# usb_and_power.net
KiCad netlist of a schematic drawn in Altium Designer
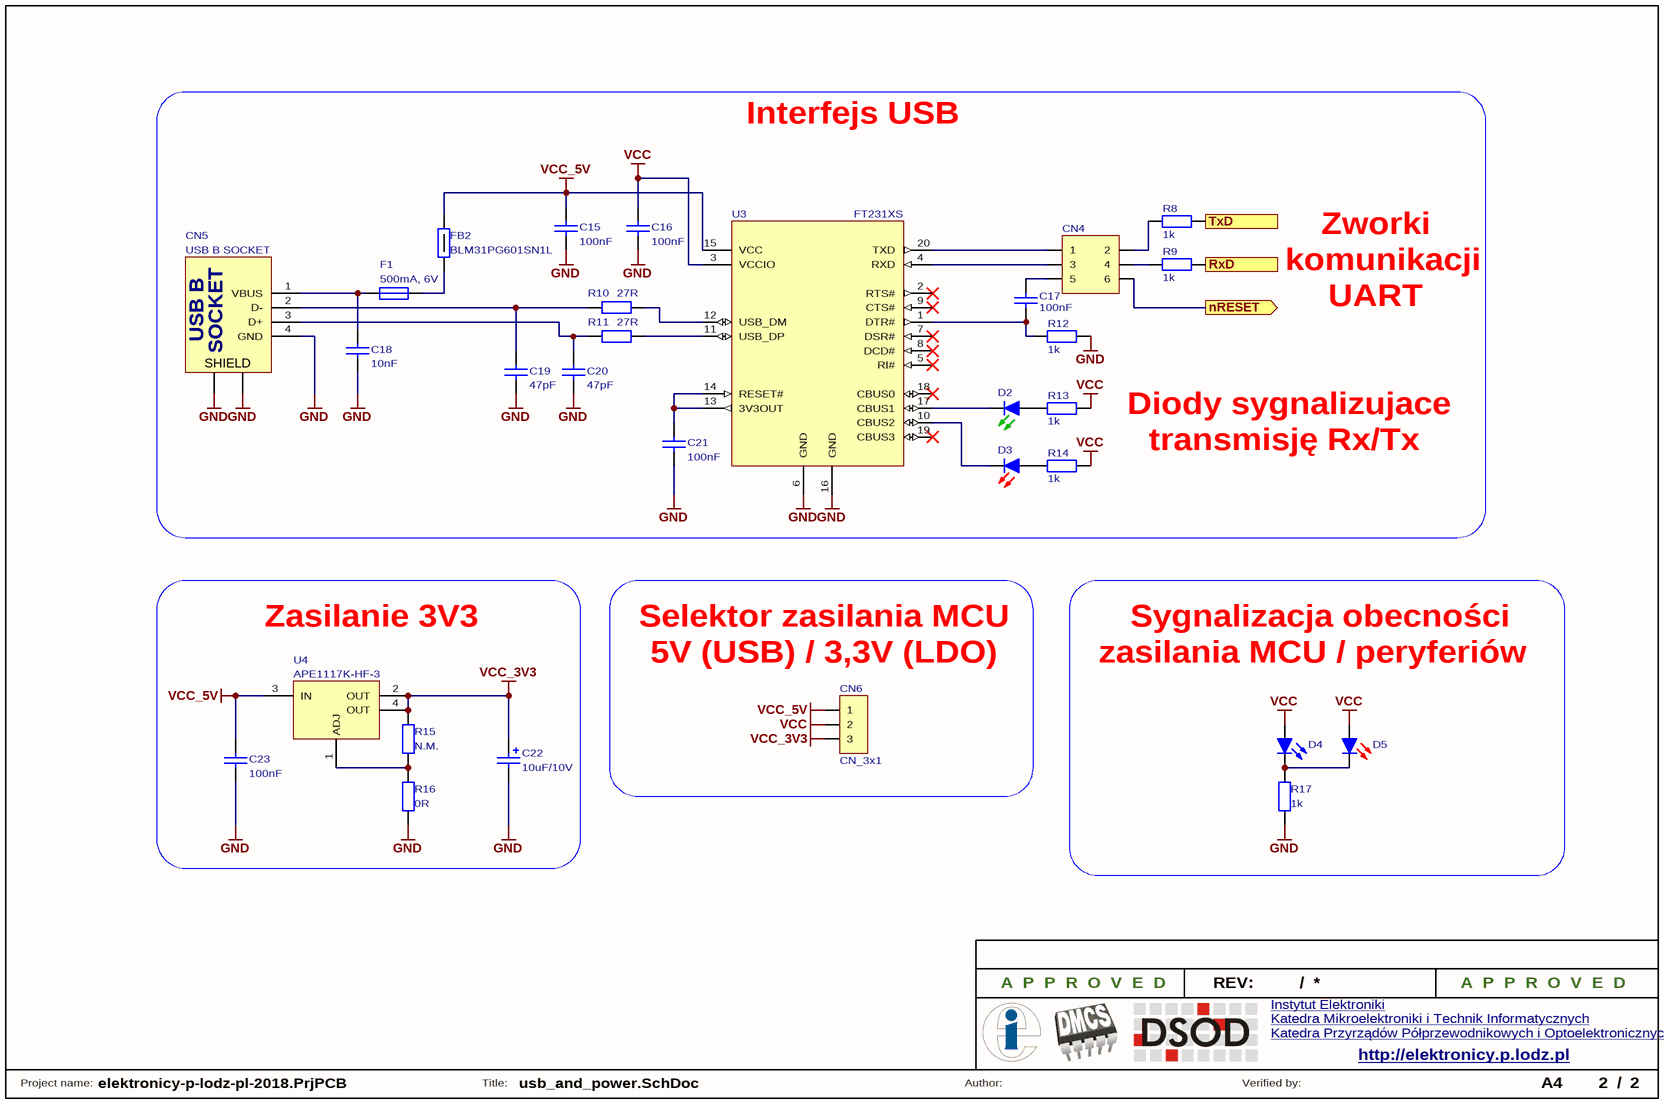
[diagram p0: usb_and_power.SchDoc]

(export (version "E")
  (design (tool "Eeschema 10.0.6"))
  (components
    (comp (ref "C15")
      (value "100nF")
      (footprint "C1206")
      (description "Capacitor")
      (libsource (lib "") (part "Cap_1"))
    )
    (comp (ref "C16")
      (value "100nF")
      (footprint "C1206")
      (description "Capacitor")
      (libsource (lib "") (part "Cap_1"))
    )
    (comp (ref "C17")
      (value "100nF")
      (footprint "C1206")
      (description "Capacitor")
      (libsource (lib "capacitors") (part "Cap"))
    )
    (comp (ref "C18")
      (value "10nF")
      (footprint "C1206")
      (description "Capacitor")
      (libsource (lib "") (part "Cap_1"))
    )
    (comp (ref "C19")
      (value "47pF")
      (footprint "C1206")
      (description "Capacitor")
      (libsource (lib "") (part "Cap_1"))
    )
    (comp (ref "C20")
      (value "47pF")
      (footprint "C1206")
      (description "Capacitor")
      (libsource (lib "") (part "Cap_1"))
    )
    (comp (ref "C21")
      (value "100nF")
      (footprint "C1206")
      (description "Capacitor")
      (libsource (lib "") (part "Cap_1"))
    )
    (comp (ref "C22")
      (value "10uF/10V")
      (footprint "SMDB")
      (description "Polarized Tantalum Capacitor")
      (libsource (lib "capacitors") (part "Cap Pol Tant"))
    )
    (comp (ref "C23")
      (value "100nF")
      (footprint "C1206")
      (description "Capacitor")
      (libsource (lib "capacitors") (part "Cap"))
    )
    (comp (ref "CN4") (value "*") (footprint "GP_3x2") (libsource (lib "goldpin_male") (part "CN_3x2")))
    (comp (ref "CN5")
      (value "USB B SOCKET")
      (footprint "USBB-G")
      (description "USB connector")
      (libsource (lib "usb") (part "USB B SOCKET"))
    )
    (comp (ref "CN6") (value "CN_3x1") (footprint "GP_3x1H") (libsource (lib "goldpin_male") (part "CN_3x1")))
    (comp (ref "D2")
      (value "*")
      (footprint "LED1206G")
      (description "GREEN LED")
      (libsource (lib "leds") (part "LED_GREEN"))
    )
    (comp (ref "D3")
      (value "*")
      (footprint "LED1206R")
      (description "RED LED")
      (libsource (lib "leds") (part "LED_RED"))
    )
    (comp (ref "D4")
      (value "LED")
      (footprint "LED-Polarized - 3mm")
      (description "Typical RED, GREEN, YELLOW, AMBER GaAs LED")
      (libsource (lib "leds") (part "LED"))
    )
    (comp (ref "D5")
      (value "*")
      (footprint "LED1206R")
      (description "RED LED")
      (libsource (lib "leds") (part "LED_RED"))
    )
    (comp (ref "F1")
      (value "500mA, 6V")
      (footprint "F1206")
      (description "500mA, 6V PTC Fuse")
      (fields (field (name "PUBLISHER") "Altium Limited"))
      (libsource (lib "fuses") (part "1206L050"))
    )
    (comp (ref "FB2")
      (value "BLM31PG601SN1L")
      (footprint "FB1206")
      (description "Ferrite Bead; Imp.@ 100MHz:600R; Mounting: SMD; 1,5A; Case: 1206")
      (libsource (lib "emi_emc_ferrites") (part "BLM31PG601SN1L"))
    )
    (comp (ref "R8")
      (value "1k")
      (footprint "R1206")
      (description "Resistor")
      (libsource (lib "") (part "Res_1"))
    )
    (comp (ref "R9")
      (value "1k")
      (footprint "R1206")
      (description "Resistor")
      (libsource (lib "") (part "Res_1"))
    )
    (comp (ref "R10")
      (value "27R")
      (footprint "R1206")
      (description "Resistor")
      (libsource (lib "") (part "Res_3"))
    )
    (comp (ref "R11")
      (value "27R")
      (footprint "R1206")
      (description "Resistor")
      (libsource (lib "") (part "Res_3"))
    )
    (comp (ref "R12")
      (value "1k")
      (footprint "R1206")
      (description "Resistor")
      (libsource (lib "") (part "Res_1"))
    )
    (comp (ref "R13")
      (value "1k")
      (footprint "R1206")
      (description "Resistor")
      (libsource (lib "") (part "Res_1"))
    )
    (comp (ref "R14")
      (value "1k")
      (footprint "R1206")
      (description "Resistor")
      (libsource (lib "") (part "Res_1"))
    )
    (comp (ref "R15")
      (value "N.M.")
      (footprint "R1206")
      (description "Resistor")
      (libsource (lib "") (part "Res_2"))
    )
    (comp (ref "R16")
      (value "0R")
      (footprint "R1206")
      (description "Resistor")
      (libsource (lib "") (part "Res_2"))
    )
    (comp (ref "R17")
      (value "1k")
      (footprint "R1206")
      (description "Resistor")
      (libsource (lib "resistors") (part "Res"))
    )
    (comp (ref "U3")
      (value "FT231XS")
      (footprint "SSOP20")
      (description "FT231X USB to UART IC")
      (libsource (lib "usb_integrated_circuits") (part "FT231XS"))
    )
    (comp (ref "U4")
      (value "APE1117K-HF-3")
      (footprint "SOT-223")
      (description "800mA Low-Dropout Adjustable, 1A Linear Regulator, SOT223 Package")
      (fields (field (name "PUBLISHER") "Altium Limited"))
      (libsource (lib "linear_voltage_regulators") (part "APE1117K-HF-3"))
    )
  )
  (nets
    (net (code "1") (name "/RxD") (class "Default")
      (node (ref "R9") (pin "1") (pinfunction "1_1") (pintype "passive"))
    )
    (net (code "2") (name "/TxD") (class "Default")
      (node (ref "R8") (pin "1") (pinfunction "1_1") (pintype "passive"))
    )
    (net (code "3") (name "/nRESET") (class "Default")
      (node (ref "CN4") (pin "6") (pinfunction "6_6") (pintype "passive"))
    )
    (net (code "4") (name "GND") (class "Default")
      (node (ref "C15") (pin "2") (pinfunction "2_2") (pintype "passive"))
      (node (ref "C16") (pin "2") (pinfunction "2_2") (pintype "passive"))
      (node (ref "C18") (pin "2") (pinfunction "2_2") (pintype "passive"))
      (node (ref "C19") (pin "1") (pinfunction "1_1") (pintype "passive"))
      (node (ref "C20") (pin "1") (pinfunction "1_1") (pintype "passive"))
      (node (ref "C21") (pin "1") (pinfunction "1_1") (pintype "passive"))
      (node (ref "C22") (pin "2") (pinfunction "2_2") (pintype "passive"))
      (node (ref "C23") (pin "1") (pinfunction "1_1") (pintype "passive"))
      (node (ref "CN5") (pin "4") (pinfunction "GND_4") (pintype "passive"))
      (node (ref "CN5") (pin "5") (pinfunction "SHIELD_5") (pintype "passive"))
      (node (ref "CN5") (pin "6") (pinfunction "SHIELD_6") (pintype "passive"))
      (node (ref "R12") (pin "1") (pinfunction "1_1") (pintype "passive"))
      (node (ref "R16") (pin "1") (pinfunction "1_1") (pintype "passive"))
      (node (ref "R17") (pin "1") (pinfunction "1_1") (pintype "passive"))
      (node (ref "U3") (pin "16") (pinfunction "GND_16") (pintype "power_in"))
      (node (ref "U3") (pin "6") (pinfunction "GND_6") (pintype "power_in"))
    )
    (net (code "5") (name "Net-(C17-Pad2)") (class "Default")
      (node (ref "C17") (pin "2") (pinfunction "2_2") (pintype "passive"))
      (node (ref "CN4") (pin "5") (pinfunction "5_5") (pintype "passive"))
    )
    (net (code "6") (name "Net-(CN4-Pad2)") (class "Default")
      (node (ref "CN4") (pin "2") (pinfunction "2_2") (pintype "passive"))
      (node (ref "R8") (pin "2") (pinfunction "2_2") (pintype "passive"))
    )
    (net (code "7") (name "Net-(CN4-Pad4)") (class "Default")
      (node (ref "CN4") (pin "4") (pinfunction "4_4") (pintype "passive"))
      (node (ref "R9") (pin "2") (pinfunction "2_2") (pintype "passive"))
    )
    (net (code "8") (name "Net-(CN5-D+)") (class "Default")
      (node (ref "C20") (pin "2") (pinfunction "2_2") (pintype "passive"))
      (node (ref "CN5") (pin "3") (pinfunction "D+_3") (pintype "passive"))
      (node (ref "R11") (pin "1") (pinfunction "1_1") (pintype "passive"))
    )
    (net (code "9") (name "Net-(CN5-D-)") (class "Default")
      (node (ref "C19") (pin "2") (pinfunction "2_2") (pintype "passive"))
      (node (ref "CN5") (pin "2") (pinfunction "D-_2") (pintype "passive"))
      (node (ref "R10") (pin "1") (pinfunction "1_1") (pintype "passive"))
    )
    (net (code "10") (name "Net-(CN5-VBUS)") (class "Default")
      (node (ref "C18") (pin "1") (pinfunction "1_1") (pintype "passive"))
      (node (ref "CN5") (pin "1") (pinfunction "VBUS_1") (pintype "passive"))
      (node (ref "F1") (pin "1") (pinfunction "1_1") (pintype "passive"))
    )
    (net (code "11") (name "Net-(D2-A)") (class "Default")
      (node (ref "D2") (pin "1") (pinfunction "A_1") (pintype "passive"))
      (node (ref "R13") (pin "2") (pinfunction "2_2") (pintype "passive"))
    )
    (net (code "12") (name "Net-(D2-K)") (class "Default")
      (node (ref "D2") (pin "2") (pinfunction "K_2") (pintype "passive"))
      (node (ref "U3") (pin "17") (pinfunction "CBUS1_17") (pintype "bidirectional"))
    )
    (net (code "13") (name "Net-(D3-A)") (class "Default")
      (node (ref "D3") (pin "1") (pinfunction "A_1") (pintype "passive"))
      (node (ref "R14") (pin "2") (pinfunction "2_2") (pintype "passive"))
    )
    (net (code "14") (name "Net-(D3-K)") (class "Default")
      (node (ref "D3") (pin "2") (pinfunction "K_2") (pintype "passive"))
      (node (ref "U3") (pin "10") (pinfunction "CBUS2_10") (pintype "bidirectional"))
    )
    (net (code "15") (name "Net-(D4-K)") (class "Default")
      (node (ref "D4") (pin "2") (pinfunction "K_2") (pintype "passive"))
      (node (ref "D5") (pin "2") (pinfunction "K_2") (pintype "passive"))
      (node (ref "R17") (pin "2") (pinfunction "2_2") (pintype "passive"))
    )
    (net (code "16") (name "Net-(F1-Pad2)") (class "Default")
      (node (ref "F1") (pin "2") (pinfunction "2_2") (pintype "passive"))
      (node (ref "FB2") (pin "2") (pinfunction "2_2") (pintype "passive"))
    )
    (net (code "17") (name "Net-(U3-3V3OUT)") (class "Default")
      (node (ref "C21") (pin "2") (pinfunction "2_2") (pintype "passive"))
      (node (ref "U3") (pin "13") (pinfunction "3V3OUT_13") (pintype "output"))
      (node (ref "U3") (pin "14") (pinfunction "RESET#_14") (pintype "input"))
    )
    (net (code "18") (name "Net-(U3-DTR#)") (class "Default")
      (node (ref "C17") (pin "1") (pinfunction "1_1") (pintype "passive"))
      (node (ref "R12") (pin "2") (pinfunction "2_2") (pintype "passive"))
      (node (ref "U3") (pin "1") (pinfunction "DTR#_1") (pintype "output"))
    )
    (net (code "19") (name "Net-(U3-RXD)") (class "Default")
      (node (ref "CN4") (pin "3") (pinfunction "3_3") (pintype "passive"))
      (node (ref "U3") (pin "4") (pinfunction "RXD_4") (pintype "input"))
    )
    (net (code "20") (name "Net-(U3-TXD)") (class "Default")
      (node (ref "CN4") (pin "1") (pinfunction "1_1") (pintype "passive"))
      (node (ref "U3") (pin "20") (pinfunction "TXD_20") (pintype "output"))
    )
    (net (code "21") (name "Net-(U3-USB_DM)") (class "Default")
      (node (ref "R10") (pin "2") (pinfunction "2_2") (pintype "passive"))
      (node (ref "U3") (pin "12") (pinfunction "USB_DM_12") (pintype "bidirectional"))
    )
    (net (code "22") (name "Net-(U3-USB_DP)") (class "Default")
      (node (ref "R11") (pin "2") (pinfunction "2_2") (pintype "passive"))
      (node (ref "U3") (pin "11") (pinfunction "USB_DP_11") (pintype "bidirectional"))
    )
    (net (code "23") (name "Net-(U4-ADJ)") (class "Default")
      (node (ref "R15") (pin "1") (pinfunction "1_1") (pintype "passive"))
      (node (ref "R16") (pin "2") (pinfunction "2_2") (pintype "passive"))
      (node (ref "U4") (pin "1") (pinfunction "ADJ_1") (pintype "power_in"))
    )
    (net (code "24") (name "VCC") (class "Default")
      (node (ref "C16") (pin "1") (pinfunction "1_1") (pintype "passive"))
      (node (ref "CN6") (pin "2") (pinfunction "2_2") (pintype "passive"))
      (node (ref "D4") (pin "1") (pinfunction "A_1") (pintype "passive"))
      (node (ref "D5") (pin "1") (pinfunction "A_1") (pintype "passive"))
      (node (ref "R13") (pin "1") (pinfunction "1_1") (pintype "passive"))
      (node (ref "R14") (pin "1") (pinfunction "1_1") (pintype "passive"))
      (node (ref "U3") (pin "3") (pinfunction "VCCIO_3") (pintype "power_in"))
    )
    (net (code "25") (name "VCC_3V3") (class "Default")
      (node (ref "C22") (pin "1") (pinfunction "1_1") (pintype "passive"))
      (node (ref "CN6") (pin "3") (pinfunction "3_3") (pintype "passive"))
      (node (ref "R15") (pin "2") (pinfunction "2_2") (pintype "passive"))
      (node (ref "U4") (pin "2") (pinfunction "OUT_2") (pintype "power_in"))
      (node (ref "U4") (pin "4") (pinfunction "OUT_4") (pintype "power_in"))
    )
    (net (code "26") (name "VCC_5V") (class "Default")
      (node (ref "C15") (pin "1") (pinfunction "1_1") (pintype "passive"))
      (node (ref "C23") (pin "2") (pinfunction "2_2") (pintype "passive"))
      (node (ref "CN6") (pin "1") (pinfunction "1_1") (pintype "passive"))
      (node (ref "FB2") (pin "1") (pinfunction "1_1") (pintype "passive"))
      (node (ref "U3") (pin "15") (pinfunction "VCC_15") (pintype "power_in"))
      (node (ref "U4") (pin "3") (pinfunction "IN_3") (pintype "power_in"))
    )
    (net (code "27") (name "unconnected-(U3-CBUS0-Pad18)") (class "Default")
      (node (ref "U3") (pin "18") (pinfunction "CBUS0_18") (pintype "bidirectional+no_connect"))
    )
    (net (code "28") (name "unconnected-(U3-CBUS3-Pad19)") (class "Default")
      (node (ref "U3") (pin "19") (pinfunction "CBUS3_19") (pintype "bidirectional+no_connect"))
    )
    (net (code "29") (name "unconnected-(U3-CTS#-Pad9)") (class "Default")
      (node (ref "U3") (pin "9") (pinfunction "CTS#_9") (pintype "input+no_connect"))
    )
    (net (code "30") (name "unconnected-(U3-DCD#-Pad8)") (class "Default")
      (node (ref "U3") (pin "8") (pinfunction "DCD#_8") (pintype "input+no_connect"))
    )
    (net (code "31") (name "unconnected-(U3-DSR#-Pad7)") (class "Default")
      (node (ref "U3") (pin "7") (pinfunction "DSR#_7") (pintype "input+no_connect"))
    )
    (net (code "32") (name "unconnected-(U3-RI#-Pad5)") (class "Default")
      (node (ref "U3") (pin "5") (pinfunction "RI#_5") (pintype "input+no_connect"))
    )
    (net (code "33") (name "unconnected-(U3-RTS#-Pad2)") (class "Default")
      (node (ref "U3") (pin "2") (pinfunction "RTS#_2") (pintype "output+no_connect"))
    )
  )
)
